# NXTMotorControl2.net
KiCad netlist of a schematic drawn in EAGLE
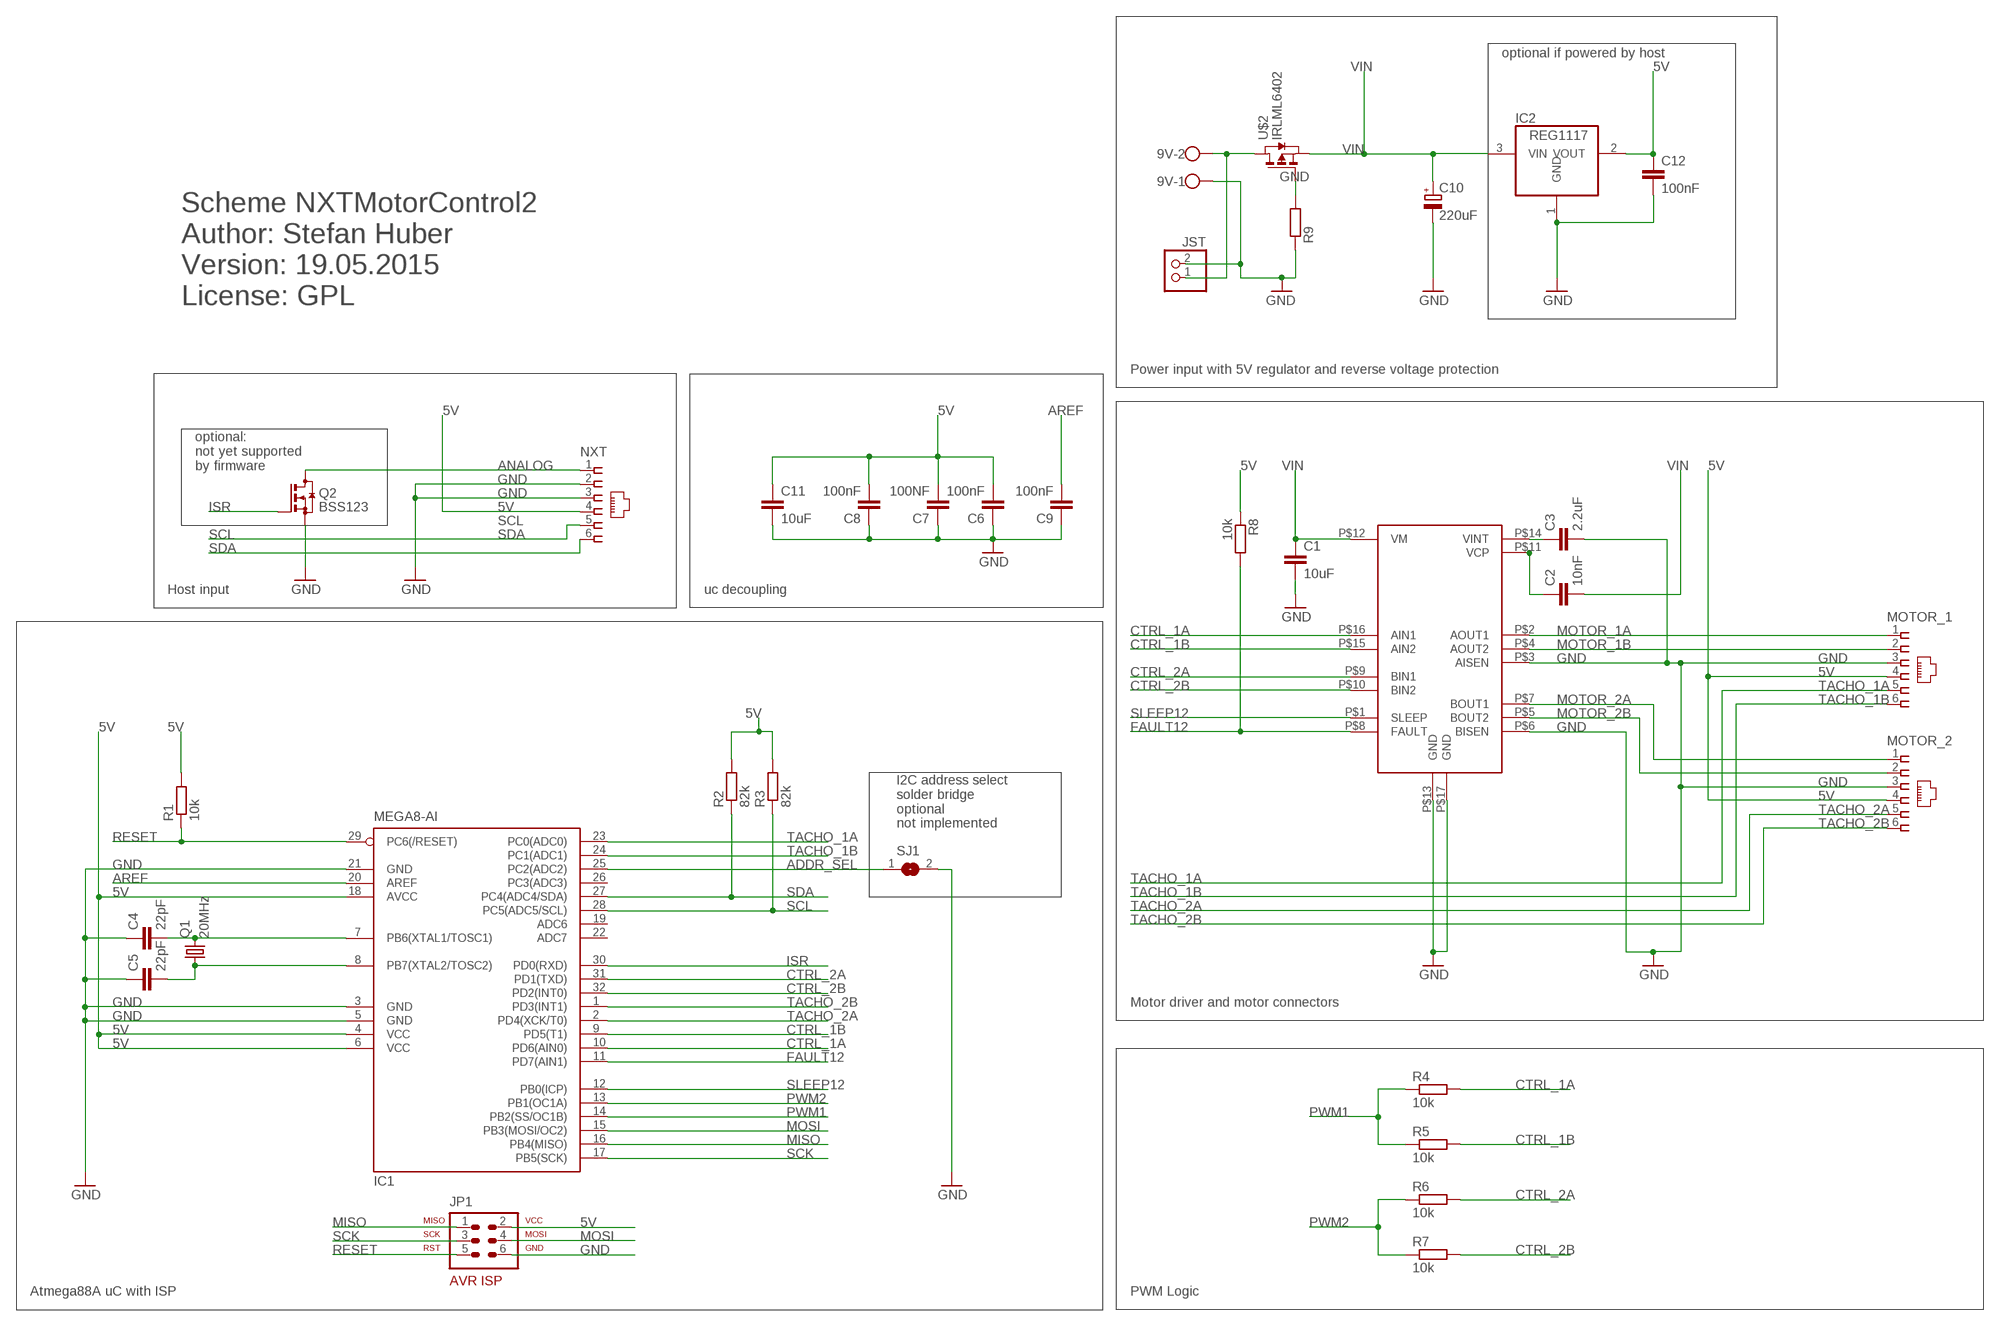
[diagram p0: schematic, sheet 1]

(export (version "E")
  (design (tool "Eeschema 10.0.6"))
  (components
    (comp (ref "9V")
      (value "W237-102")
      (footprint "eagle-import:W237-102")
      (fields (field (name "MPN") "237-102"))
      (libsource (lib "eagle-import") (part "W237-102"))
    )
    (comp (ref "C1")
      (value "10uF")
      (footprint "eagle-import:C0805")
      (libsource (lib "eagle-import") (part "C-EUC0805"))
    )
    (comp (ref "C2")
      (value "10nF")
      (footprint "eagle-import:C0805")
      (libsource (lib "eagle-import") (part "C-EUC0805"))
    )
    (comp (ref "C3")
      (value "2.2uF")
      (footprint "eagle-import:C0805")
      (libsource (lib "eagle-import") (part "C-EUC0805"))
    )
    (comp (ref "C4")
      (value "22pF")
      (footprint "eagle-import:C0805")
      (libsource (lib "eagle-import") (part "resistor_C-EUC0805"))
    )
    (comp (ref "C5")
      (value "22pF")
      (footprint "eagle-import:C0805")
      (libsource (lib "eagle-import") (part "resistor_C-EUC0805"))
    )
    (comp (ref "C6")
      (value "100nF")
      (footprint "eagle-import:C0805")
      (libsource (lib "eagle-import") (part "resistor_C-EUC0805"))
    )
    (comp (ref "C7")
      (value "100NF")
      (footprint "eagle-import:C0805")
      (libsource (lib "eagle-import") (part "resistor_C-EUC0805"))
    )
    (comp (ref "C8")
      (value "100nF")
      (footprint "eagle-import:C0805")
      (libsource (lib "eagle-import") (part "resistor_C-EUC0805"))
    )
    (comp (ref "C9")
      (value "100nF")
      (footprint "eagle-import:C0805")
      (libsource (lib "eagle-import") (part "resistor_C-EUC0805"))
    )
    (comp (ref "C10")
      (value "220uF")
      (footprint "eagle-import:E3,5-8")
      (libsource (lib "eagle-import") (part "CPOL-EUE3.5-8"))
    )
    (comp (ref "C11")
      (value "10uF")
      (footprint "eagle-import:C0805")
      (libsource (lib "eagle-import") (part "resistor_C-EUC0805"))
    )
    (comp (ref "C12")
      (value "100nF")
      (footprint "eagle-import:C0805")
      (libsource (lib "eagle-import") (part "C-EUC0805"))
    )
    (comp (ref "IC1")
      (value "MEGA8-AI")
      (footprint "eagle-import:TQFP32-08")
      (fields (field (name "MPN") "ATMEGA8-16AU"))
      (libsource (lib "eagle-import") (part "MEGA8-AI"))
    )
    (comp (ref "IC2")
      (value "REG1117")
      (footprint "eagle-import:SOT223")
      (libsource (lib "eagle-import") (part "REG1117"))
    )
    (comp (ref "JP1")
      (value "ISP")
      (footprint "eagle-import:AVR-ISP-6")
      (libsource (lib "eagle-import") (part "AVR-ISP-6VERT"))
    )
    (comp (ref "JST")
      (value "JST_2PIN-THM")
      (footprint "eagle-import:JST-PH-2-THM")
      (libsource (lib "eagle-import") (part "JST_2PIN-THM"))
    )
    (comp (ref "MOTOR_1")
      (value "NXT")
      (footprint "eagle-import:NXT")
      (libsource (lib "eagle-import") (part "NXT"))
    )
    (comp (ref "MOTOR_2")
      (value "NXT")
      (footprint "eagle-import:NXT")
      (libsource (lib "eagle-import") (part "NXT"))
    )
    (comp (ref "NXT")
      (value "NXT")
      (footprint "eagle-import:NXT")
      (libsource (lib "eagle-import") (part "NXT"))
    )
    (comp (ref "Q1")
      (value "20MHz")
      (footprint "eagle-import:HC49_S")
      (libsource (lib "eagle-import") (part "CRYSTALHC49S"))
    )
    (comp (ref "Q2")
      (value "BSS123")
      (footprint "eagle-import:SOT23")
      (libsource (lib "eagle-import") (part "BSS123"))
    )
    (comp (ref "R1")
      (value "10k")
      (footprint "eagle-import:R0805")
      (libsource (lib "eagle-import") (part "R-EU_R0805"))
    )
    (comp (ref "R2")
      (value "82k")
      (footprint "eagle-import:R0805")
      (libsource (lib "eagle-import") (part "R-EU_R0805"))
    )
    (comp (ref "R3")
      (value "82k")
      (footprint "eagle-import:R0805")
      (libsource (lib "eagle-import") (part "R-EU_R0805"))
    )
    (comp (ref "R4")
      (value "10k")
      (footprint "eagle-import:R0805")
      (libsource (lib "eagle-import") (part "R-EU_R0805"))
    )
    (comp (ref "R5")
      (value "10k")
      (footprint "eagle-import:R0805")
      (libsource (lib "eagle-import") (part "R-EU_R0805"))
    )
    (comp (ref "R6")
      (value "10k")
      (footprint "eagle-import:R0805")
      (libsource (lib "eagle-import") (part "R-EU_R0805"))
    )
    (comp (ref "R7")
      (value "10k")
      (footprint "eagle-import:R0805")
      (libsource (lib "eagle-import") (part "R-EU_R0805"))
    )
    (comp (ref "R8")
      (value "10k")
      (footprint "eagle-import:R0805")
      (libsource (lib "eagle-import") (part "R-EU_R0805"))
    )
    (comp (ref "R9")
      (value "R-EU_R0805")
      (footprint "eagle-import:R0805")
      (libsource (lib "eagle-import") (part "R-EU_R0805"))
    )
    (comp (ref "SJ1") (value "SJ") (footprint "eagle-import:SJ") (libsource (lib "eagle-import") (part "SJ")))
    (comp (ref "U$1")
      (value "DRV8833")
      (footprint "eagle-import:HTSSOP16")
      (libsource (lib "eagle-import") (part "DRV8833"))
    )
    (comp (ref "U$2")
      (value "IRLML6402")
      (footprint "eagle-import:SOT-23")
      (libsource (lib "eagle-import") (part "IRLML6402"))
    )
  )
  (nets
    (net (code "1") (name "/5V") (class "Default")
      (node (ref "C11") (pin "1") (pinfunction "1_1") (pintype "passive"))
      (node (ref "C12") (pin "1") (pinfunction "1_1") (pintype "passive"))
      (node (ref "C6") (pin "2") (pinfunction "2_2") (pintype "passive"))
      (node (ref "C7") (pin "2") (pinfunction "2_2") (pintype "passive"))
      (node (ref "C8") (pin "2") (pinfunction "2_2") (pintype "passive"))
      (node (ref "IC1") (pin "18") (pinfunction "AVCC_18") (pintype "power_in"))
      (node (ref "IC1") (pin "4") (pinfunction "VCC_4") (pintype "power_in"))
      (node (ref "IC1") (pin "6") (pinfunction "VCC_6") (pintype "power_in"))
      (node (ref "IC2") (pin "2") (pinfunction "VOUT_2") (pintype "output"))
      (node (ref "JP1") (pin "2") (pinfunction "2_2") (pintype "passive"))
      (node (ref "MOTOR_1") (pin "4") (pinfunction "4_4") (pintype "passive"))
      (node (ref "MOTOR_2") (pin "4") (pinfunction "4_4") (pintype "passive"))
      (node (ref "NXT") (pin "4") (pinfunction "4_4") (pintype "passive"))
      (node (ref "R1") (pin "2") (pinfunction "2_2") (pintype "passive"))
      (node (ref "R2") (pin "2") (pinfunction "2_2") (pintype "passive"))
      (node (ref "R3") (pin "2") (pinfunction "2_2") (pintype "passive"))
      (node (ref "R8") (pin "1") (pinfunction "1_1") (pintype "passive"))
    )
    (net (code "2") (name "/ADDR_SEL") (class "Default")
      (node (ref "IC1") (pin "25") (pinfunction "PC2(ADC2)_25") (pintype "bidirectional"))
      (node (ref "SJ1") (pin "1") (pinfunction "1_1") (pintype "passive"))
    )
    (net (code "3") (name "/ANALOG") (class "Default")
      (node (ref "NXT") (pin "1") (pinfunction "1_1") (pintype "passive"))
      (node (ref "Q2") (pin "3") (pinfunction "D_3") (pintype "passive"))
    )
    (net (code "4") (name "/AREF") (class "Default")
      (node (ref "C9") (pin "2") (pinfunction "2_2") (pintype "passive"))
      (node (ref "IC1") (pin "20") (pinfunction "AREF_20") (pintype "passive"))
    )
    (net (code "5") (name "/CTRL_1A") (class "Default")
      (node (ref "IC1") (pin "10") (pinfunction "PD6(AIN0)_10") (pintype "bidirectional"))
      (node (ref "R4") (pin "2") (pinfunction "2_2") (pintype "passive"))
      (node (ref "U$1") (pin "P$16") (pinfunction "AIN1_P$16") (pintype "bidirectional"))
    )
    (net (code "6") (name "/CTRL_1B") (class "Default")
      (node (ref "IC1") (pin "9") (pinfunction "PD5(T1)_9") (pintype "bidirectional"))
      (node (ref "R5") (pin "2") (pinfunction "2_2") (pintype "passive"))
      (node (ref "U$1") (pin "P$15") (pinfunction "AIN2_P$15") (pintype "bidirectional"))
    )
    (net (code "7") (name "/CTRL_2A") (class "Default")
      (node (ref "IC1") (pin "31") (pinfunction "PD1(TXD)_31") (pintype "bidirectional"))
      (node (ref "R6") (pin "2") (pinfunction "2_2") (pintype "passive"))
      (node (ref "U$1") (pin "P$9") (pinfunction "BIN1_P$9") (pintype "bidirectional"))
    )
    (net (code "8") (name "/CTRL_2B") (class "Default")
      (node (ref "IC1") (pin "32") (pinfunction "PD2(INT0)_32") (pintype "bidirectional"))
      (node (ref "R7") (pin "2") (pinfunction "2_2") (pintype "passive"))
      (node (ref "U$1") (pin "P$10") (pinfunction "BIN2_P$10") (pintype "bidirectional"))
    )
    (net (code "9") (name "/FAULT12") (class "Default")
      (node (ref "IC1") (pin "11") (pinfunction "PD7(AIN1)_11") (pintype "bidirectional"))
      (node (ref "R8") (pin "2") (pinfunction "2_2") (pintype "passive"))
      (node (ref "U$1") (pin "P$8") (pinfunction "FAULT_P$8") (pintype "bidirectional"))
    )
    (net (code "10") (name "/ISR") (class "Default")
      (node (ref "IC1") (pin "30") (pinfunction "PD0(RXD)_30") (pintype "bidirectional"))
      (node (ref "Q2") (pin "1") (pinfunction "G_1") (pintype "passive"))
    )
    (net (code "11") (name "/MISO") (class "Default")
      (node (ref "IC1") (pin "16") (pinfunction "PB4(MISO)_16") (pintype "bidirectional"))
      (node (ref "JP1") (pin "1") (pinfunction "1_1") (pintype "passive"))
    )
    (net (code "12") (name "/MOSI") (class "Default")
      (node (ref "IC1") (pin "15") (pinfunction "PB3(MOSI/OC2)_15") (pintype "bidirectional"))
      (node (ref "JP1") (pin "4") (pinfunction "4_4") (pintype "passive"))
    )
    (net (code "13") (name "/MOTOR_1A") (class "Default")
      (node (ref "MOTOR_1") (pin "1") (pinfunction "1_1") (pintype "passive"))
      (node (ref "U$1") (pin "P$2") (pinfunction "AOUT1_P$2") (pintype "bidirectional"))
    )
    (net (code "14") (name "/MOTOR_1B") (class "Default")
      (node (ref "MOTOR_1") (pin "2") (pinfunction "2_2") (pintype "passive"))
      (node (ref "U$1") (pin "P$4") (pinfunction "AOUT2_P$4") (pintype "bidirectional"))
    )
    (net (code "15") (name "/MOTOR_2A") (class "Default")
      (node (ref "MOTOR_2") (pin "1") (pinfunction "1_1") (pintype "passive"))
      (node (ref "U$1") (pin "P$7") (pinfunction "BOUT1_P$7") (pintype "bidirectional"))
    )
    (net (code "16") (name "/MOTOR_2B") (class "Default")
      (node (ref "MOTOR_2") (pin "2") (pinfunction "2_2") (pintype "passive"))
      (node (ref "U$1") (pin "P$5") (pinfunction "BOUT2_P$5") (pintype "bidirectional"))
    )
    (net (code "17") (name "/PWM1") (class "Default")
      (node (ref "IC1") (pin "14") (pinfunction "PB2(SS/OC1B)_14") (pintype "bidirectional"))
      (node (ref "R4") (pin "1") (pinfunction "1_1") (pintype "passive"))
      (node (ref "R5") (pin "1") (pinfunction "1_1") (pintype "passive"))
    )
    (net (code "18") (name "/PWM2") (class "Default")
      (node (ref "IC1") (pin "13") (pinfunction "PB1(OC1A)_13") (pintype "bidirectional"))
      (node (ref "R6") (pin "1") (pinfunction "1_1") (pintype "passive"))
      (node (ref "R7") (pin "1") (pinfunction "1_1") (pintype "passive"))
    )
    (net (code "19") (name "/RESET") (class "Default")
      (node (ref "IC1") (pin "29") (pinfunction "PC6(/RESET)_29") (pintype "bidirectional"))
      (node (ref "JP1") (pin "5") (pinfunction "5_5") (pintype "passive"))
      (node (ref "R1") (pin "1") (pinfunction "1_1") (pintype "passive"))
    )
    (net (code "20") (name "/SCK") (class "Default")
      (node (ref "IC1") (pin "17") (pinfunction "PB5(SCK)_17") (pintype "bidirectional"))
      (node (ref "JP1") (pin "3") (pinfunction "3_3") (pintype "passive"))
    )
    (net (code "21") (name "/SCL") (class "Default")
      (node (ref "IC1") (pin "28") (pinfunction "PC5(ADC5/SCL)_28") (pintype "bidirectional"))
      (node (ref "NXT") (pin "5") (pinfunction "5_5") (pintype "passive"))
      (node (ref "R3") (pin "1") (pinfunction "1_1") (pintype "passive"))
    )
    (net (code "22") (name "/SDA") (class "Default")
      (node (ref "IC1") (pin "27") (pinfunction "PC4(ADC4/SDA)_27") (pintype "bidirectional"))
      (node (ref "NXT") (pin "6") (pinfunction "6_6") (pintype "passive"))
      (node (ref "R2") (pin "1") (pinfunction "1_1") (pintype "passive"))
    )
    (net (code "23") (name "/SLEEP12") (class "Default")
      (node (ref "IC1") (pin "12") (pinfunction "PB0(ICP)_12") (pintype "bidirectional"))
      (node (ref "U$1") (pin "P$1") (pinfunction "SLEEP_P$1") (pintype "bidirectional"))
    )
    (net (code "24") (name "/TACHO_1A") (class "Default")
      (node (ref "IC1") (pin "23") (pinfunction "PC0(ADC0)_23") (pintype "bidirectional"))
      (node (ref "MOTOR_1") (pin "5") (pinfunction "5_5") (pintype "passive"))
    )
    (net (code "25") (name "/TACHO_1B") (class "Default")
      (node (ref "IC1") (pin "24") (pinfunction "PC1(ADC1)_24") (pintype "bidirectional"))
      (node (ref "MOTOR_1") (pin "6") (pinfunction "6_6") (pintype "passive"))
    )
    (net (code "26") (name "/TACHO_2A") (class "Default")
      (node (ref "IC1") (pin "2") (pinfunction "PD4(XCK/T0)_2") (pintype "bidirectional"))
      (node (ref "MOTOR_2") (pin "5") (pinfunction "5_5") (pintype "passive"))
    )
    (net (code "27") (name "/TACHO_2B") (class "Default")
      (node (ref "IC1") (pin "1") (pinfunction "PD3(INT1)_1") (pintype "bidirectional"))
      (node (ref "MOTOR_2") (pin "6") (pinfunction "6_6") (pintype "passive"))
    )
    (net (code "28") (name "/VIN") (class "Default")
      (node (ref "C1") (pin "1") (pinfunction "1_1") (pintype "passive"))
      (node (ref "C10") (pin "+") (pinfunction "+_+") (pintype "passive"))
      (node (ref "C2") (pin "2") (pinfunction "2_2") (pintype "passive"))
      (node (ref "IC2") (pin "3") (pinfunction "VIN_3") (pintype "input"))
      (node (ref "U$1") (pin "P$12") (pinfunction "VM_P$12") (pintype "bidirectional"))
      (node (ref "U$2") (pin "2") (pinfunction "S_2") (pintype "passive"))
    )
    (net (code "29") (name "GND") (class "Default")
      (node (ref "9V") (pin "1") (pinfunction "KL_1") (pintype "passive"))
      (node (ref "C1") (pin "2") (pinfunction "2_2") (pintype "passive"))
      (node (ref "C10") (pin "-") (pinfunction "-_-") (pintype "passive"))
      (node (ref "C11") (pin "2") (pinfunction "2_2") (pintype "passive"))
      (node (ref "C12") (pin "2") (pinfunction "2_2") (pintype "passive"))
      (node (ref "C3") (pin "2") (pinfunction "2_2") (pintype "passive"))
      (node (ref "C4") (pin "1") (pinfunction "1_1") (pintype "passive"))
      (node (ref "C5") (pin "1") (pinfunction "1_1") (pintype "passive"))
      (node (ref "C6") (pin "1") (pinfunction "1_1") (pintype "passive"))
      (node (ref "C7") (pin "1") (pinfunction "1_1") (pintype "passive"))
      (node (ref "C8") (pin "1") (pinfunction "1_1") (pintype "passive"))
      (node (ref "C9") (pin "1") (pinfunction "1_1") (pintype "passive"))
      (node (ref "IC1") (pin "21") (pinfunction "GND_21") (pintype "power_in"))
      (node (ref "IC1") (pin "3") (pinfunction "GND_3") (pintype "power_in"))
      (node (ref "IC1") (pin "5") (pinfunction "GND_5") (pintype "power_in"))
      (node (ref "IC2") (pin "1") (pinfunction "GND_1") (pintype "power_in"))
      (node (ref "JP1") (pin "6") (pinfunction "6_6") (pintype "passive"))
      (node (ref "JST") (pin "2") (pinfunction "1_2") (pintype "passive"))
      (node (ref "MOTOR_1") (pin "3") (pinfunction "3_3") (pintype "passive"))
      (node (ref "MOTOR_2") (pin "3") (pinfunction "3_3") (pintype "passive"))
      (node (ref "NXT") (pin "2") (pinfunction "2_2") (pintype "passive"))
      (node (ref "NXT") (pin "3") (pinfunction "3_3") (pintype "passive"))
      (node (ref "Q2") (pin "2") (pinfunction "S_2") (pintype "passive"))
      (node (ref "R9") (pin "1") (pinfunction "1_1") (pintype "passive"))
      (node (ref "SJ1") (pin "2") (pinfunction "2_2") (pintype "passive"))
      (node (ref "U$1") (pin "P$13") (pinfunction "GND_P$13") (pintype "bidirectional"))
      (node (ref "U$1") (pin "P$17") (pinfunction "GND_P$17") (pintype "bidirectional"))
      (node (ref "U$1") (pin "P$3") (pinfunction "AISEN_P$3") (pintype "bidirectional"))
      (node (ref "U$1") (pin "P$6") (pinfunction "BISEN_P$6") (pintype "bidirectional"))
    )
    (net (code "30") (name "Net-(9VB-KL)") (class "Default")
      (node (ref "9V") (pin "2") (pinfunction "KL_2") (pintype "passive"))
      (node (ref "JST") (pin "1") (pinfunction "2_1") (pintype "passive"))
      (node (ref "U$2") (pin "3") (pinfunction "D_3") (pintype "passive"))
    )
    (net (code "31") (name "Net-(IC1-PB6(XTAL1{slash}TOSC1))") (class "Default")
      (node (ref "C4") (pin "2") (pinfunction "2_2") (pintype "passive"))
      (node (ref "IC1") (pin "7") (pinfunction "PB6(XTAL1/TOSC1)_7") (pintype "bidirectional"))
      (node (ref "Q1") (pin "2") (pinfunction "2_2") (pintype "passive"))
    )
    (net (code "32") (name "Net-(IC1-PB7(XTAL2{slash}TOSC2))") (class "Default")
      (node (ref "C5") (pin "2") (pinfunction "2_2") (pintype "passive"))
      (node (ref "IC1") (pin "8") (pinfunction "PB7(XTAL2/TOSC2)_8") (pintype "bidirectional"))
      (node (ref "Q1") (pin "1") (pinfunction "1_1") (pintype "passive"))
    )
    (net (code "33") (name "Net-(U$1-VCP)") (class "Default")
      (node (ref "C2") (pin "1") (pinfunction "1_1") (pintype "passive"))
      (node (ref "U$1") (pin "P$11") (pinfunction "VCP_P$11") (pintype "bidirectional"))
    )
    (net (code "34") (name "Net-(U$1-VINT)") (class "Default")
      (node (ref "C3") (pin "1") (pinfunction "1_1") (pintype "passive"))
      (node (ref "U$1") (pin "P$14") (pinfunction "VINT_P$14") (pintype "bidirectional"))
    )
    (net (code "35") (name "Net-(U$2-G)") (class "Default")
      (node (ref "R9") (pin "2") (pinfunction "2_2") (pintype "passive"))
      (node (ref "U$2") (pin "1") (pinfunction "G_1") (pintype "passive"))
    )
    (net (code "36") (name "unconnected-(IC1-ADC6-Pad19)") (class "Default")
      (node (ref "IC1") (pin "19") (pinfunction "ADC6_19") (pintype "bidirectional"))
    )
    (net (code "37") (name "unconnected-(IC1-ADC7-Pad22)") (class "Default")
      (node (ref "IC1") (pin "22") (pinfunction "ADC7_22") (pintype "bidirectional"))
    )
    (net (code "38") (name "unconnected-(IC1-PC3(ADC3)-Pad26)") (class "Default")
      (node (ref "IC1") (pin "26") (pinfunction "PC3(ADC3)_26") (pintype "bidirectional"))
    )
  )
)
